# peripherals.net
KiCad netlist of a schematic drawn in Altium Designer
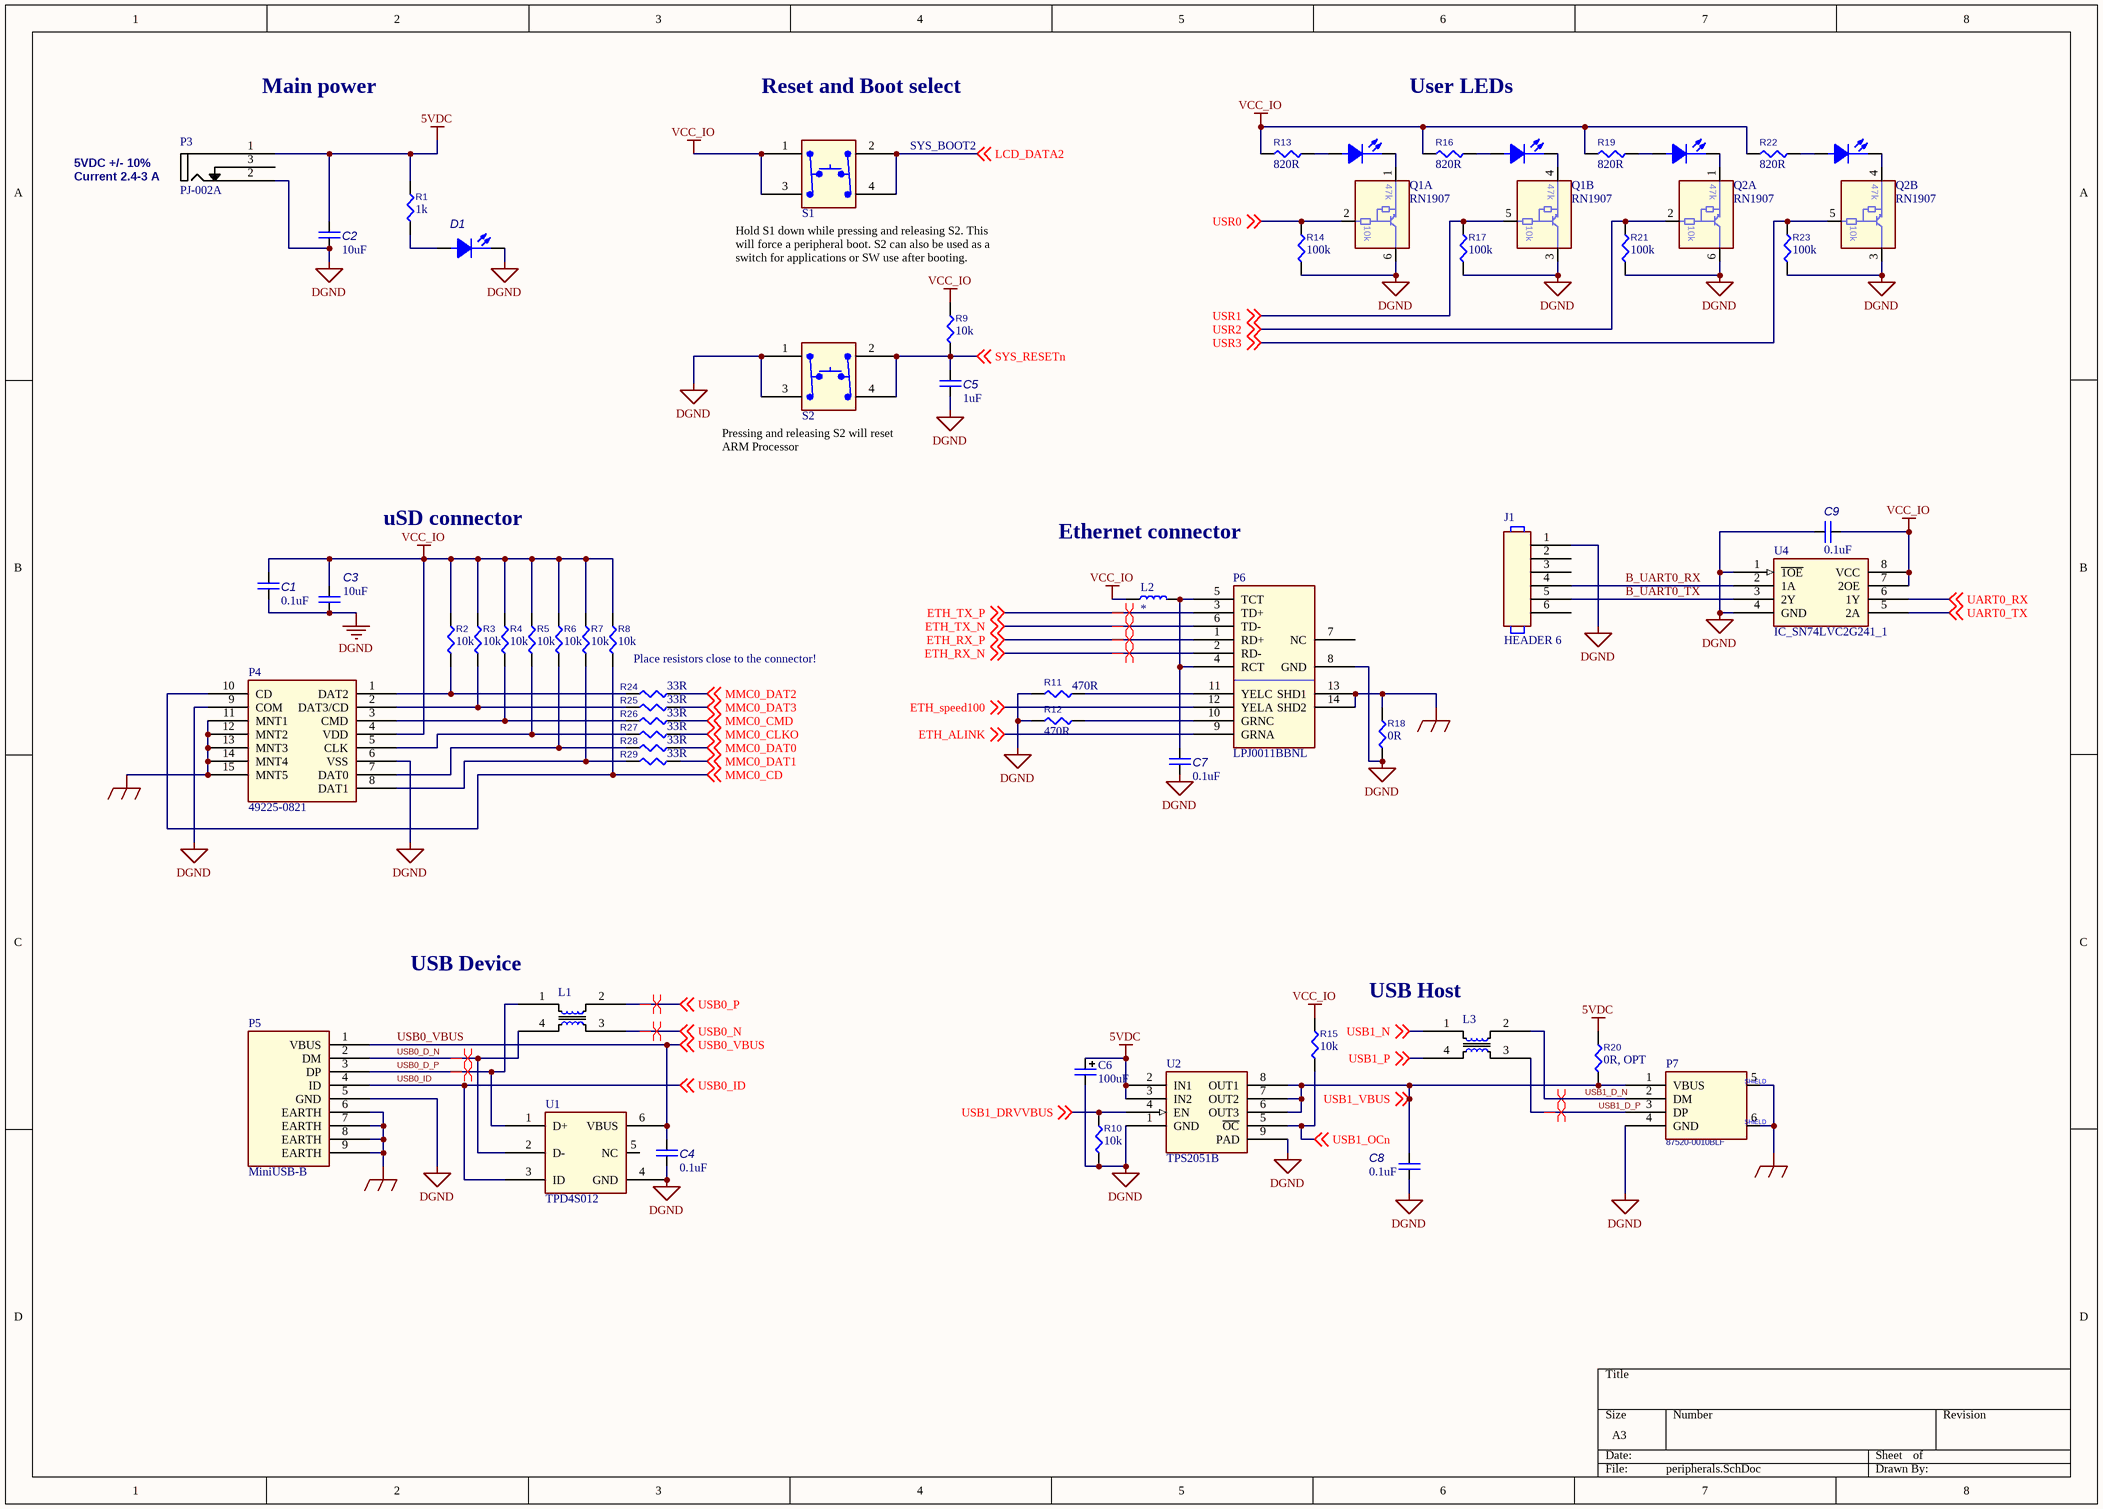
[diagram p0: peripherals.SchDoc]

(export (version "E")
  (design (tool "Eeschema 10.0.6"))
  (components
    (comp (ref "C1")
      (value "0.1uF")
      (footprint "CC1608-0603")
      (description "C0603")
      (libsource (lib "am335x-base") (part "C0603"))
    )
    (comp (ref "C2")
      (value "10uF")
      (footprint "CC2012-0805")
      (description "C0805")
      (libsource (lib "am335x-base") (part "C0805"))
    )
    (comp (ref "C3")
      (value "10uF")
      (footprint "CC2012-0805")
      (description "C0805")
      (libsource (lib "am335x-base") (part "C0805"))
    )
    (comp (ref "C4")
      (value "0.1uF")
      (footprint "CC1608-0603")
      (description "C0603")
      (libsource (lib "am335x-base") (part "C0603"))
    )
    (comp (ref "C5")
      (value "1uF")
      (footprint "CC1608-0603")
      (description "C0603")
      (libsource (lib "am335x-base") (part "C0603"))
    )
    (comp (ref "C6")
      (value "100uF")
      (footprint "Cap_C")
      (description "Tantalum Capacitor Case C")
      (fields (field (name "Comment") "Cap_C"))
      (libsource (lib "am335x-base") (part "Cap_C"))
    )
    (comp (ref "C7")
      (value "0.1uF")
      (footprint "CC1608-0603")
      (description "C0603")
      (libsource (lib "am335x-base") (part "C0603"))
    )
    (comp (ref "C8")
      (value "0.1uF")
      (footprint "CC1608-0603")
      (description "C0603")
      (libsource (lib "am335x-base") (part "C0603"))
    )
    (comp (ref "C9")
      (value "0.1uF")
      (footprint "CC1608-0603")
      (description "C0603")
      (libsource (lib "usomiq-base") (part "C0603"))
    )
    (comp (ref "D1")
      (value "LED0805")
      (footprint "LED0805")
      (description "LED 0805")
      (libsource (lib "am335x-base") (part "LED0805"))
    )
    (comp (ref "D2")
      (value "LED0805")
      (footprint "LED0805")
      (description "LED 0805")
      (libsource (lib "am335x-base") (part "LED0805"))
    )
    (comp (ref "D3")
      (value "LED0805")
      (footprint "LED0805")
      (description "LED 0805")
      (libsource (lib "am335x-base") (part "LED0805"))
    )
    (comp (ref "D4")
      (value "LED0805")
      (footprint "LED0805")
      (description "LED 0805")
      (libsource (lib "am335x-base") (part "LED0805"))
    )
    (comp (ref "D5")
      (value "LED0805")
      (footprint "LED0805")
      (description "LED 0805")
      (libsource (lib "am335x-base") (part "LED0805"))
    )
    (comp (ref "J1")
      (value "HEADER 6")
      (footprint "DIP6")
      (description "CONN HEADER 6POS, VERTICAL,  .100 STR TIN")
      (fields (field (name "MFR") "FCI"))
      (libsource (lib "usomiq-base") (part "HEADER 6"))
    )
    (comp (ref "L1")
      (value "DLW21H")
      (footprint "DLW21H")
      (description "Low profile wire-wound common choke coil")
      (fields (field (name "MANUFACTURER") "Murata"))
      (libsource (lib "am335x-base") (part "DLW21H"))
    )
    (comp (ref "L2")
      (value "BLM18A-FB")
      (footprint "CHIP0603")
      (description "Chip EMIFILr Inductor Type")
      (fields (field (name "MANUFACTURER") "Murata") (field (name "MAN P/N") "*"))
      (libsource (lib "am335x-base") (part "BLM18A-FB"))
    )
    (comp (ref "L3")
      (value "DLW21H")
      (footprint "DLW21H")
      (description "Low profile wire-wound common choke coil")
      (fields (field (name "MANUFACTURER") "Murata"))
      (libsource (lib "am335x-base") (part "DLW21H"))
    )
    (comp (ref "P3")
      (value "PJ-002A")
      (footprint "PJ-002A")
      (description "DC POWER JACK")
      (fields (field (name "MANUFACTURER") "CIU Inc"))
      (libsource (lib "omap") (part "PJ-002A"))
    )
    (comp (ref "P4")
      (value "49225-0821")
      (footprint "SDCard")
      (description "Connector for microSD™ Card (Push-push Type)")
      (fields (field (name "MANUFACTURER") "Molex"))
      (libsource (lib "am335x-base") (part "Mol_49225-0821"))
    )
    (comp (ref "P5")
      (value "MiniUSB-B")
      (footprint "MINI-USB-B5 SMT")
      (description "Mini USB Type B CONNECTOR")
      (fields (field (name "MFR") "Hirose"))
      (libsource (lib "usomiq-base") (part "MiniUSB-B"))
    )
    (comp (ref "P6")
      (value "CONN_RJ45_MAG_WE_0")
      (footprint "TRJ0011ABNL")
      (description "RJ-45 10/100 W/Magnetics")
      (fields (field (name "MFR") "Link PP") (field (name "P/N") "LPJ0011BBNL"))
      (libsource (lib "am335x-base") (part "CONN_RJ45_MAG_WE_0"))
    )
    (comp (ref "P7")
      (value "CONN_54819-0578_2")
      (footprint "USB2.5-2H4C")
      (description "USB Type A Connectors")
      (fields (field (name "P/N") "87520-0010BLF") (field (name "MFR") "FCI"))
      (libsource (lib "am335x-base") (part "CONN_54819-0578_2"))
    )
    (comp (ref "Q1")
      (value "RN1907")
      (footprint "SOT363-6L")
      (description "Transistor Silicon NPN")
      (fields (field (name "MFR") "Panasonic"))
      (libsource (lib "am335x-base") (part "RN1907"))
    )
    (comp (ref "Q2")
      (value "RN1907")
      (footprint "SOT363-6L")
      (description "Transistor Silicon NPN")
      (fields (field (name "MFR") "Panasonic"))
      (libsource (lib "am335x-base") (part "RN1907"))
    )
    (comp (ref "R1")
      (value "1k")
      (footprint "RESC1608X55N")
      (description "R0603")
      (libsource (lib "am335x-base") (part "R0603"))
    )
    (comp (ref "R2")
      (value "10k")
      (footprint "RESC1608X55N")
      (description "R0603")
      (libsource (lib "am335x-base") (part "R0603"))
    )
    (comp (ref "R3")
      (value "10k")
      (footprint "RESC1608X55N")
      (description "R0603")
      (libsource (lib "am335x-base") (part "R0603"))
    )
    (comp (ref "R4")
      (value "10k")
      (footprint "RESC1608X55N")
      (description "R0603")
      (libsource (lib "am335x-base") (part "R0603"))
    )
    (comp (ref "R5")
      (value "10k")
      (footprint "RESC1608X55N")
      (description "R0603")
      (libsource (lib "am335x-base") (part "R0603"))
    )
    (comp (ref "R6")
      (value "10k")
      (footprint "RESC1608X55N")
      (description "R0603")
      (libsource (lib "am335x-base") (part "R0603"))
    )
    (comp (ref "R7")
      (value "10k")
      (footprint "RESC1608X55N")
      (description "R0603")
      (libsource (lib "am335x-base") (part "R0603"))
    )
    (comp (ref "R8")
      (value "10k")
      (footprint "RESC1608X55N")
      (description "R0603")
      (libsource (lib "am335x-base") (part "R0603"))
    )
    (comp (ref "R9")
      (value "10k")
      (footprint "RESC1608X55N")
      (description "R0603")
      (libsource (lib "am335x-base") (part "R0603"))
    )
    (comp (ref "R10")
      (value "10k")
      (footprint "RESC1608X55N")
      (description "R0603")
      (libsource (lib "am335x-base") (part "R0603"))
    )
    (comp (ref "R11")
      (value "470R")
      (footprint "RESC1608X55N")
      (description "R0603")
      (libsource (lib "am335x-base") (part "R0603"))
    )
    (comp (ref "R12")
      (value "470R")
      (footprint "RESC1608X55N")
      (description "R0603")
      (libsource (lib "am335x-base") (part "R0603"))
    )
    (comp (ref "R13")
      (value "820R")
      (footprint "RESC1608X55N")
      (description "R0603")
      (libsource (lib "am335x-base") (part "R0603"))
    )
    (comp (ref "R14")
      (value "100k")
      (footprint "RESC1608X55N")
      (description "R0603")
      (libsource (lib "am335x-base") (part "R0603"))
    )
    (comp (ref "R15")
      (value "10k")
      (footprint "RESC1608X55N")
      (description "R0603")
      (libsource (lib "am335x-base") (part "R0603"))
    )
    (comp (ref "R16")
      (value "820R")
      (footprint "RESC1608X55N")
      (description "R0603")
      (libsource (lib "am335x-base") (part "R0603"))
    )
    (comp (ref "R17")
      (value "100k")
      (footprint "RESC1608X55N")
      (description "R0603")
      (libsource (lib "am335x-base") (part "R0603"))
    )
    (comp (ref "R18")
      (value "0R")
      (footprint "RESC1608X55N")
      (description "R0603")
      (libsource (lib "am335x-base") (part "R0603"))
    )
    (comp (ref "R19")
      (value "820R")
      (footprint "RESC1608X55N")
      (description "R0603")
      (libsource (lib "am335x-base") (part "R0603"))
    )
    (comp (ref "R20")
      (value "0R, OPT")
      (footprint "RESC1608X55N")
      (description "R0603")
      (libsource (lib "am335x-base") (part "R0603"))
    )
    (comp (ref "R21")
      (value "100k")
      (footprint "RESC1608X55N")
      (description "R0603")
      (libsource (lib "am335x-base") (part "R0603"))
    )
    (comp (ref "R22")
      (value "820R")
      (footprint "RESC1608X55N")
      (description "R0603")
      (libsource (lib "am335x-base") (part "R0603"))
    )
    (comp (ref "R23")
      (value "100k")
      (footprint "RESC1608X55N")
      (description "R0603")
      (libsource (lib "am335x-base") (part "R0603"))
    )
    (comp (ref "R24")
      (value "33R")
      (footprint "RESC1608X55N")
      (description "R0603")
      (libsource (lib "usomiq-base") (part "R0603"))
    )
    (comp (ref "R25")
      (value "33R")
      (footprint "RESC1608X55N")
      (description "R0603")
      (libsource (lib "usomiq-base") (part "R0603"))
    )
    (comp (ref "R26")
      (value "33R")
      (footprint "RESC1608X55N")
      (description "R0603")
      (libsource (lib "usomiq-base") (part "R0603"))
    )
    (comp (ref "R27")
      (value "33R")
      (footprint "RESC1608X55N")
      (description "R0603")
      (libsource (lib "usomiq-base") (part "R0603"))
    )
    (comp (ref "R28")
      (value "33R")
      (footprint "RESC1608X55N")
      (description "R0603")
      (libsource (lib "usomiq-base") (part "R0603"))
    )
    (comp (ref "R29")
      (value "33R")
      (footprint "RESC1608X55N")
      (description "R0603")
      (libsource (lib "usomiq-base") (part "R0603"))
    )
    (comp (ref "S1")
      (value "SW_KT11P2JM_2")
      (footprint "KMR231GLFS")
      (description "SMD button")
      (fields (field (name "MFR") "C&K Components"))
      (libsource (lib "usomiq-base") (part "SW_KT11P2JM_2"))
    )
    (comp (ref "S2")
      (value "SW_KT11P2JM_2")
      (footprint "KMR231GLFS")
      (description "SMD button")
      (fields (field (name "MFR") "C&K Components"))
      (libsource (lib "usomiq-base") (part "SW_KT11P2JM_2"))
    )
    (comp (ref "U1")
      (value "TPD4S012")
      (footprint "s-puson-n6")
      (description "4-Channel USB ESD Solution with Power Clamp")
      (fields (field (name "MFR") "TI"))
      (libsource (lib "usomiq-base") (part "TPD4S012"))
    )
    (comp (ref "U2")
      (value "TPS2051B")
      (footprint "R-PDSO-G8")
      (description "CURRENT-LIMITED, POWER-DISTRIBUTION SWITCHES")
      (fields (field (name "MFR") "TI"))
      (libsource (lib "usomiq-base") (part "TPS2051B"))
    )
    (comp (ref "U4")
      (value "IC_SN74LVC2G241_1")
      (footprint "SOP127P600-8N")
      (description "Dual Buffer/Driver With 3-State Outputs")
      (fields (field (name "MFR") "TI"))
      (libsource (lib "usomiq-base") (part "IC_SN74LVC2G241_1"))
    )
  )
  (nets
    (net (code "1") (name "/B_UART0_RX") (class "Default")
      (node (ref "J1") (pin "4") (pinfunction "4_4") (pintype "passive"))
      (node (ref "U4") (pin "2") (pinfunction "1A_2") (pintype "passive"))
    )
    (net (code "2") (name "/B_UART0_TX") (class "Default")
      (node (ref "J1") (pin "5") (pinfunction "5_5") (pintype "passive"))
      (node (ref "U4") (pin "3") (pinfunction "2Y_3") (pintype "passive"))
    )
    (net (code "3") (name "/USB0_D_N") (class "Default")
      (node (ref "L1") (pin "4") (pinfunction "4_4") (pintype "passive"))
      (node (ref "P5") (pin "2") (pinfunction "DM_2") (pintype "passive"))
      (node (ref "U1") (pin "2") (pinfunction "D-_2") (pintype "passive"))
    )
    (net (code "4") (name "/USB0_D_P") (class "Default")
      (node (ref "L1") (pin "1") (pinfunction "1_1") (pintype "passive"))
      (node (ref "P5") (pin "3") (pinfunction "DP_3") (pintype "passive"))
      (node (ref "U1") (pin "1") (pinfunction "D+_1") (pintype "passive"))
    )
    (net (code "5") (name "/USB1_D_N") (class "Default")
      (node (ref "L3") (pin "2") (pinfunction "2_2") (pintype "passive"))
      (node (ref "P7") (pin "2") (pinfunction "DM_2") (pintype "passive"))
    )
    (net (code "6") (name "/USB1_D_P") (class "Default")
      (node (ref "L3") (pin "3") (pinfunction "3_3") (pintype "passive"))
      (node (ref "P7") (pin "3") (pinfunction "DP_3") (pintype "passive"))
    )
    (net (code "7") (name "5VDC") (class "Default")
      (node (ref "C2") (pin "2") (pinfunction "2_2") (pintype "passive"))
      (node (ref "C6") (pin "1") (pinfunction "1_1") (pintype "passive"))
      (node (ref "P3") (pin "1") (pinfunction "GND_1") (pintype "passive"))
      (node (ref "R1") (pin "2") (pinfunction "2_2") (pintype "passive"))
      (node (ref "R20") (pin "2") (pinfunction "2_2") (pintype "passive"))
      (node (ref "U2") (pin "2") (pinfunction "IN1_2") (pintype "power_in"))
      (node (ref "U2") (pin "3") (pinfunction "IN2_3") (pintype "power_in"))
    )
    (net (code "8") (name "DGND") (class "Default")
      (node (ref "C1") (pin "2") (pinfunction "2_2") (pintype "passive"))
      (node (ref "C2") (pin "1") (pinfunction "1_1") (pintype "passive"))
      (node (ref "C3") (pin "1") (pinfunction "1_1") (pintype "passive"))
      (node (ref "C4") (pin "2") (pinfunction "2_2") (pintype "passive"))
      (node (ref "C5") (pin "2") (pinfunction "2_2") (pintype "passive"))
      (node (ref "C6") (pin "2") (pinfunction "2_2") (pintype "passive"))
      (node (ref "C7") (pin "2") (pinfunction "2_2") (pintype "passive"))
      (node (ref "C8") (pin "1") (pinfunction "1_1") (pintype "passive"))
      (node (ref "C9") (pin "1") (pinfunction "1_1") (pintype "passive"))
      (node (ref "D1") (pin "2") (pinfunction "C_2") (pintype "passive"))
      (node (ref "J1") (pin "1") (pinfunction "1_1") (pintype "passive"))
      (node (ref "P3") (pin "2") (pinfunction "RIGHT_2") (pintype "passive"))
      (node (ref "P4") (pin "6") (pinfunction "VSS_6") (pintype "power_in"))
      (node (ref "P4") (pin "9") (pinfunction "COM_9") (pintype "passive"))
      (node (ref "P5") (pin "5") (pinfunction "GND_5") (pintype "power_in"))
      (node (ref "P6") (pin "8") (pinfunction "GND_8") (pintype "passive"))
      (node (ref "P7") (pin "4") (pinfunction "GND_4") (pintype "passive"))
      (node (ref "Q1") (pin "3") (pinfunction "3_3") (pintype "passive"))
      (node (ref "Q1") (pin "6") (pinfunction "3_6") (pintype "passive"))
      (node (ref "Q2") (pin "3") (pinfunction "3_3") (pintype "passive"))
      (node (ref "Q2") (pin "6") (pinfunction "3_6") (pintype "passive"))
      (node (ref "R10") (pin "1") (pinfunction "1_1") (pintype "passive"))
      (node (ref "R11") (pin "1") (pinfunction "1_1") (pintype "passive"))
      (node (ref "R12") (pin "1") (pinfunction "1_1") (pintype "passive"))
      (node (ref "R14") (pin "1") (pinfunction "1_1") (pintype "passive"))
      (node (ref "R17") (pin "1") (pinfunction "1_1") (pintype "passive"))
      (node (ref "R18") (pin "1") (pinfunction "1_1") (pintype "passive"))
      (node (ref "R21") (pin "1") (pinfunction "1_1") (pintype "passive"))
      (node (ref "R23") (pin "1") (pinfunction "1_1") (pintype "passive"))
      (node (ref "S2") (pin "1") (pinfunction "A1_1") (pintype "passive"))
      (node (ref "S2") (pin "3") (pinfunction "A2_3") (pintype "passive"))
      (node (ref "U1") (pin "4") (pinfunction "GND_4") (pintype "power_in"))
      (node (ref "U2") (pin "1") (pinfunction "GND_1") (pintype "power_in"))
      (node (ref "U2") (pin "9") (pinfunction "PAD_9") (pintype "passive"))
      (node (ref "U4") (pin "1") (pinfunction "~{1OE}_1") (pintype "input"))
      (node (ref "U4") (pin "4") (pinfunction "GND_4") (pintype "power_in"))
    )
    (net (code "9") (name "EARTH") (class "Default")
      (node (ref "P4") (pin "11") (pinfunction "MNT1_11") (pintype "passive"))
      (node (ref "P4") (pin "12") (pinfunction "MNT2_12") (pintype "passive"))
      (node (ref "P4") (pin "13") (pinfunction "MNT3_13") (pintype "passive"))
      (node (ref "P4") (pin "14") (pinfunction "MNT4_14") (pintype "passive"))
      (node (ref "P4") (pin "15") (pinfunction "MNT5_15") (pintype "passive"))
      (node (ref "P5") (pin "6") (pinfunction "EARTH_6") (pintype "passive"))
      (node (ref "P5") (pin "7") (pinfunction "EARTH_7") (pintype "passive"))
      (node (ref "P5") (pin "8") (pinfunction "EARTH_8") (pintype "passive"))
      (node (ref "P5") (pin "9") (pinfunction "EARTH_9") (pintype "passive"))
      (node (ref "P6") (pin "13") (pinfunction "SHD1_13") (pintype "passive"))
      (node (ref "P6") (pin "14") (pinfunction "SHD2_14") (pintype "passive"))
      (node (ref "P7") (pin "5") (pinfunction "SHELD1_5") (pintype "passive"))
      (node (ref "P7") (pin "6") (pinfunction "PAD4_6") (pintype "passive"))
      (node (ref "R18") (pin "2") (pinfunction "2_2") (pintype "passive"))
    )
    (net (code "10") (name "ETH_ALINK") (class "Default")
      (node (ref "P6") (pin "9") (pinfunction "GRNA_9") (pintype "passive"))
    )
    (net (code "11") (name "ETH_RX_N") (class "Default")
      (node (ref "P6") (pin "2") (pinfunction "RD-_2") (pintype "passive"))
    )
    (net (code "12") (name "ETH_RX_P") (class "Default")
      (node (ref "P6") (pin "1") (pinfunction "RD+_1") (pintype "passive"))
    )
    (net (code "13") (name "ETH_TX_N") (class "Default")
      (node (ref "P6") (pin "6") (pinfunction "TD-_6") (pintype "passive"))
    )
    (net (code "14") (name "ETH_TX_P") (class "Default")
      (node (ref "P6") (pin "3") (pinfunction "TD+_3") (pintype "passive"))
    )
    (net (code "15") (name "ETH_speed100") (class "Default")
      (node (ref "P6") (pin "12") (pinfunction "YELA_12") (pintype "passive"))
    )
    (net (code "16") (name "LCD_DATA2") (class "Default")
      (node (ref "S1") (pin "2") (pinfunction "B1_2") (pintype "passive"))
      (node (ref "S1") (pin "4") (pinfunction "B2_4") (pintype "passive"))
    )
    (net (code "17") (name "MMC0_CD") (class "Default")
      (node (ref "P4") (pin "10") (pinfunction "CD_10") (pintype "passive"))
      (node (ref "R8") (pin "1") (pinfunction "1_1") (pintype "passive"))
    )
    (net (code "18") (name "MMC0_CLKO") (class "Default")
      (node (ref "R27") (pin "2") (pinfunction "2_2") (pintype "passive"))
    )
    (net (code "19") (name "MMC0_CMD") (class "Default")
      (node (ref "R26") (pin "2") (pinfunction "2_2") (pintype "passive"))
    )
    (net (code "20") (name "MMC0_DAT0") (class "Default")
      (node (ref "R28") (pin "2") (pinfunction "2_2") (pintype "passive"))
    )
    (net (code "21") (name "MMC0_DAT1") (class "Default")
      (node (ref "R29") (pin "2") (pinfunction "2_2") (pintype "passive"))
    )
    (net (code "22") (name "MMC0_DAT2") (class "Default")
      (node (ref "R24") (pin "2") (pinfunction "2_2") (pintype "passive"))
    )
    (net (code "23") (name "MMC0_DAT3") (class "Default")
      (node (ref "R25") (pin "2") (pinfunction "2_2") (pintype "passive"))
    )
    (net (code "24") (name "Net-(D1-A)") (class "Default")
      (node (ref "D1") (pin "1") (pinfunction "A_1") (pintype "passive"))
      (node (ref "R1") (pin "1") (pinfunction "1_1") (pintype "passive"))
    )
    (net (code "25") (name "Net-(D2-A)") (class "Default")
      (node (ref "D2") (pin "1") (pinfunction "A_1") (pintype "passive"))
      (node (ref "R13") (pin "1") (pinfunction "1_1") (pintype "passive"))
    )
    (net (code "26") (name "Net-(D2-C)") (class "Default")
      (node (ref "D2") (pin "2") (pinfunction "C_2") (pintype "passive"))
      (node (ref "Q1") (pin "1") (pinfunction "4_1") (pintype "passive"))
    )
    (net (code "27") (name "Net-(D3-A)") (class "Default")
      (node (ref "D3") (pin "1") (pinfunction "A_1") (pintype "passive"))
      (node (ref "R16") (pin "1") (pinfunction "1_1") (pintype "passive"))
    )
    (net (code "28") (name "Net-(D3-C)") (class "Default")
      (node (ref "D3") (pin "2") (pinfunction "C_2") (pintype "passive"))
      (node (ref "Q1") (pin "4") (pinfunction "4_4") (pintype "passive"))
    )
    (net (code "29") (name "Net-(D4-A)") (class "Default")
      (node (ref "D4") (pin "1") (pinfunction "A_1") (pintype "passive"))
      (node (ref "R19") (pin "1") (pinfunction "1_1") (pintype "passive"))
    )
    (net (code "30") (name "Net-(D4-C)") (class "Default")
      (node (ref "D4") (pin "2") (pinfunction "C_2") (pintype "passive"))
      (node (ref "Q2") (pin "1") (pinfunction "4_1") (pintype "passive"))
    )
    (net (code "31") (name "Net-(D5-A)") (class "Default")
      (node (ref "D5") (pin "1") (pinfunction "A_1") (pintype "passive"))
      (node (ref "R22") (pin "1") (pinfunction "1_1") (pintype "passive"))
    )
    (net (code "32") (name "Net-(D5-C)") (class "Default")
      (node (ref "D5") (pin "2") (pinfunction "C_2") (pintype "passive"))
      (node (ref "Q2") (pin "4") (pinfunction "4_4") (pintype "passive"))
    )
    (net (code "33") (name "Net-(P4-CLK)") (class "Default")
      (node (ref "P4") (pin "5") (pinfunction "CLK_5") (pintype "passive"))
      (node (ref "R27") (pin "1") (pinfunction "1_1") (pintype "passive"))
      (node (ref "R5") (pin "1") (pinfunction "1_1") (pintype "passive"))
    )
    (net (code "34") (name "Net-(P4-CMD)") (class "Default")
      (node (ref "P4") (pin "3") (pinfunction "CMD_3") (pintype "passive"))
      (node (ref "R26") (pin "1") (pinfunction "1_1") (pintype "passive"))
      (node (ref "R4") (pin "1") (pinfunction "1_1") (pintype "passive"))
    )
    (net (code "35") (name "Net-(P4-DAT0)") (class "Default")
      (node (ref "P4") (pin "7") (pinfunction "DAT0_7") (pintype "passive"))
      (node (ref "R28") (pin "1") (pinfunction "1_1") (pintype "passive"))
      (node (ref "R6") (pin "1") (pinfunction "1_1") (pintype "passive"))
    )
    (net (code "36") (name "Net-(P4-DAT1)") (class "Default")
      (node (ref "P4") (pin "8") (pinfunction "DAT1_8") (pintype "passive"))
      (node (ref "R29") (pin "1") (pinfunction "1_1") (pintype "passive"))
      (node (ref "R7") (pin "1") (pinfunction "1_1") (pintype "passive"))
    )
    (net (code "37") (name "Net-(P4-DAT2)") (class "Default")
      (node (ref "P4") (pin "1") (pinfunction "DAT2_1") (pintype "passive"))
      (node (ref "R2") (pin "1") (pinfunction "1_1") (pintype "passive"))
      (node (ref "R24") (pin "1") (pinfunction "1_1") (pintype "passive"))
    )
    (net (code "38") (name "Net-(P4-DAT3{slash}CD)") (class "Default")
      (node (ref "P4") (pin "2") (pinfunction "DAT3/CD_2") (pintype "passive"))
      (node (ref "R25") (pin "1") (pinfunction "1_1") (pintype "passive"))
      (node (ref "R3") (pin "1") (pinfunction "1_1") (pintype "passive"))
    )
    (net (code "39") (name "Net-(P6-GRNC)") (class "Default")
      (node (ref "P6") (pin "10") (pinfunction "GRNC_10") (pintype "passive"))
      (node (ref "R12") (pin "2") (pinfunction "2_2") (pintype "passive"))
    )
    (net (code "40") (name "Net-(P6-RCT)") (class "Default")
      (node (ref "C7") (pin "1") (pinfunction "1_1") (pintype "passive"))
      (node (ref "L2") (pin "2") (pinfunction "2_2") (pintype "passive"))
      (node (ref "P6") (pin "4") (pinfunction "RCT_4") (pintype "passive"))
      (node (ref "P6") (pin "5") (pinfunction "TCT_5") (pintype "passive"))
    )
    (net (code "41") (name "Net-(P6-YELC)") (class "Default")
      (node (ref "P6") (pin "11") (pinfunction "YELC_11") (pintype "passive"))
      (node (ref "R11") (pin "2") (pinfunction "2_2") (pintype "passive"))
    )
    (net (code "42") (name "SYS_RESETn") (class "Default")
      (node (ref "C5") (pin "1") (pinfunction "1_1") (pintype "passive"))
      (node (ref "R9") (pin "1") (pinfunction "1_1") (pintype "passive"))
      (node (ref "S2") (pin "2") (pinfunction "B1_2") (pintype "passive"))
      (node (ref "S2") (pin "4") (pinfunction "B2_4") (pintype "passive"))
    )
    (net (code "43") (name "UART0_RX") (class "Default")
      (node (ref "U4") (pin "6") (pinfunction "1Y_6") (pintype "passive"))
    )
    (net (code "44") (name "UART0_TX") (class "Default")
      (node (ref "U4") (pin "5") (pinfunction "2A_5") (pintype "passive"))
    )
    (net (code "45") (name "USB0_ID") (class "Default")
      (node (ref "P5") (pin "4") (pinfunction "ID_4") (pintype "passive"))
      (node (ref "U1") (pin "3") (pinfunction "ID_3") (pintype "passive"))
    )
    (net (code "46") (name "USB0_N") (class "Default")
      (node (ref "L1") (pin "3") (pinfunction "3_3") (pintype "passive"))
    )
    (net (code "47") (name "USB0_P") (class "Default")
      (node (ref "L1") (pin "2") (pinfunction "2_2") (pintype "passive"))
    )
    (net (code "48") (name "USB0_VBUS") (class "Default")
      (node (ref "C4") (pin "1") (pinfunction "1_1") (pintype "passive"))
      (node (ref "P5") (pin "1") (pinfunction "VBUS_1") (pintype "power_in"))
      (node (ref "U1") (pin "6") (pinfunction "VBUS_6") (pintype "power_in"))
    )
    (net (code "49") (name "USB1_DRVVBUS") (class "Default")
      (node (ref "R10") (pin "2") (pinfunction "2_2") (pintype "passive"))
      (node (ref "U2") (pin "4") (pinfunction "EN_4") (pintype "input"))
    )
    (net (code "50") (name "USB1_N") (class "Default")
      (node (ref "L3") (pin "1") (pinfunction "1_1") (pintype "passive"))
    )
    (net (code "51") (name "USB1_OCn") (class "Default")
      (node (ref "R15") (pin "1") (pinfunction "1_1") (pintype "passive"))
      (node (ref "U2") (pin "5") (pinfunction "~{OC}_5") (pintype "passive"))
    )
    (net (code "52") (name "USB1_P") (class "Default")
      (node (ref "L3") (pin "4") (pinfunction "4_4") (pintype "passive"))
    )
    (net (code "53") (name "USB1_VBUS") (class "Default")
      (node (ref "C8") (pin "2") (pinfunction "2_2") (pintype "passive"))
      (node (ref "P7") (pin "1") (pinfunction "VBUS_1") (pintype "passive"))
      (node (ref "R20") (pin "1") (pinfunction "1_1") (pintype "passive"))
      (node (ref "U2") (pin "6") (pinfunction "OUT3_6") (pintype "power_in"))
      (node (ref "U2") (pin "7") (pinfunction "OUT2_7") (pintype "power_in"))
      (node (ref "U2") (pin "8") (pinfunction "OUT1_8") (pintype "power_in"))
    )
    (net (code "54") (name "USR0") (class "Default")
      (node (ref "Q1") (pin "2") (pinfunction "5_2") (pintype "passive"))
      (node (ref "R14") (pin "2") (pinfunction "2_2") (pintype "passive"))
    )
    (net (code "55") (name "USR1") (class "Default")
      (node (ref "Q1") (pin "5") (pinfunction "5_5") (pintype "passive"))
      (node (ref "R17") (pin "2") (pinfunction "2_2") (pintype "passive"))
    )
    (net (code "56") (name "USR2") (class "Default")
      (node (ref "Q2") (pin "2") (pinfunction "5_2") (pintype "passive"))
      (node (ref "R21") (pin "2") (pinfunction "2_2") (pintype "passive"))
    )
    (net (code "57") (name "USR3") (class "Default")
      (node (ref "Q2") (pin "5") (pinfunction "5_5") (pintype "passive"))
      (node (ref "R23") (pin "2") (pinfunction "2_2") (pintype "passive"))
    )
    (net (code "58") (name "VCC_IO") (class "Default")
      (node (ref "C1") (pin "1") (pinfunction "1_1") (pintype "passive"))
      (node (ref "C3") (pin "2") (pinfunction "2_2") (pintype "passive"))
      (node (ref "C9") (pin "2") (pinfunction "2_2") (pintype "passive"))
      (node (ref "L2") (pin "1") (pinfunction "1_1") (pintype "passive"))
      (node (ref "P4") (pin "4") (pinfunction "VDD_4") (pintype "power_in"))
      (node (ref "R13") (pin "2") (pinfunction "2_2") (pintype "passive"))
      (node (ref "R15") (pin "2") (pinfunction "2_2") (pintype "passive"))
      (node (ref "R16") (pin "2") (pinfunction "2_2") (pintype "passive"))
      (node (ref "R19") (pin "2") (pinfunction "2_2") (pintype "passive"))
      (node (ref "R2") (pin "2") (pinfunction "2_2") (pintype "passive"))
      (node (ref "R22") (pin "2") (pinfunction "2_2") (pintype "passive"))
      (node (ref "R3") (pin "2") (pinfunction "2_2") (pintype "passive"))
      (node (ref "R4") (pin "2") (pinfunction "2_2") (pintype "passive"))
      (node (ref "R5") (pin "2") (pinfunction "2_2") (pintype "passive"))
      (node (ref "R6") (pin "2") (pinfunction "2_2") (pintype "passive"))
      (node (ref "R7") (pin "2") (pinfunction "2_2") (pintype "passive"))
      (node (ref "R8") (pin "2") (pinfunction "2_2") (pintype "passive"))
      (node (ref "R9") (pin "2") (pinfunction "2_2") (pintype "passive"))
      (node (ref "S1") (pin "1") (pinfunction "A1_1") (pintype "passive"))
      (node (ref "S1") (pin "3") (pinfunction "A2_3") (pintype "passive"))
      (node (ref "U4") (pin "7") (pinfunction "2OE_7") (pintype "passive"))
      (node (ref "U4") (pin "8") (pinfunction "VCC_8") (pintype "power_in"))
    )
    (net (code "59") (name "unconnected-(J1-Pad2)") (class "Default")
      (node (ref "J1") (pin "2") (pinfunction "2_2") (pintype "passive"))
    )
    (net (code "60") (name "unconnected-(J1-Pad3)") (class "Default")
      (node (ref "J1") (pin "3") (pinfunction "3_3") (pintype "passive"))
    )
    (net (code "61") (name "unconnected-(J1-Pad6)") (class "Default")
      (node (ref "J1") (pin "6") (pinfunction "6_6") (pintype "passive"))
    )
    (net (code "62") (name "unconnected-(P3-LEFT-Pad3)") (class "Default")
      (node (ref "P3") (pin "3") (pinfunction "LEFT_3") (pintype "passive"))
    )
    (net (code "63") (name "unconnected-(P6-NC-Pad7)") (class "Default")
      (node (ref "P6") (pin "7") (pinfunction "NC_7") (pintype "passive"))
    )
    (net (code "64") (name "unconnected-(U1-NC-Pad5)") (class "Default")
      (node (ref "U1") (pin "5") (pinfunction "NC_5") (pintype "passive"))
    )
  )
)
